# DMSMDS.net
KiCad netlist of a schematic drawn in EAGLE
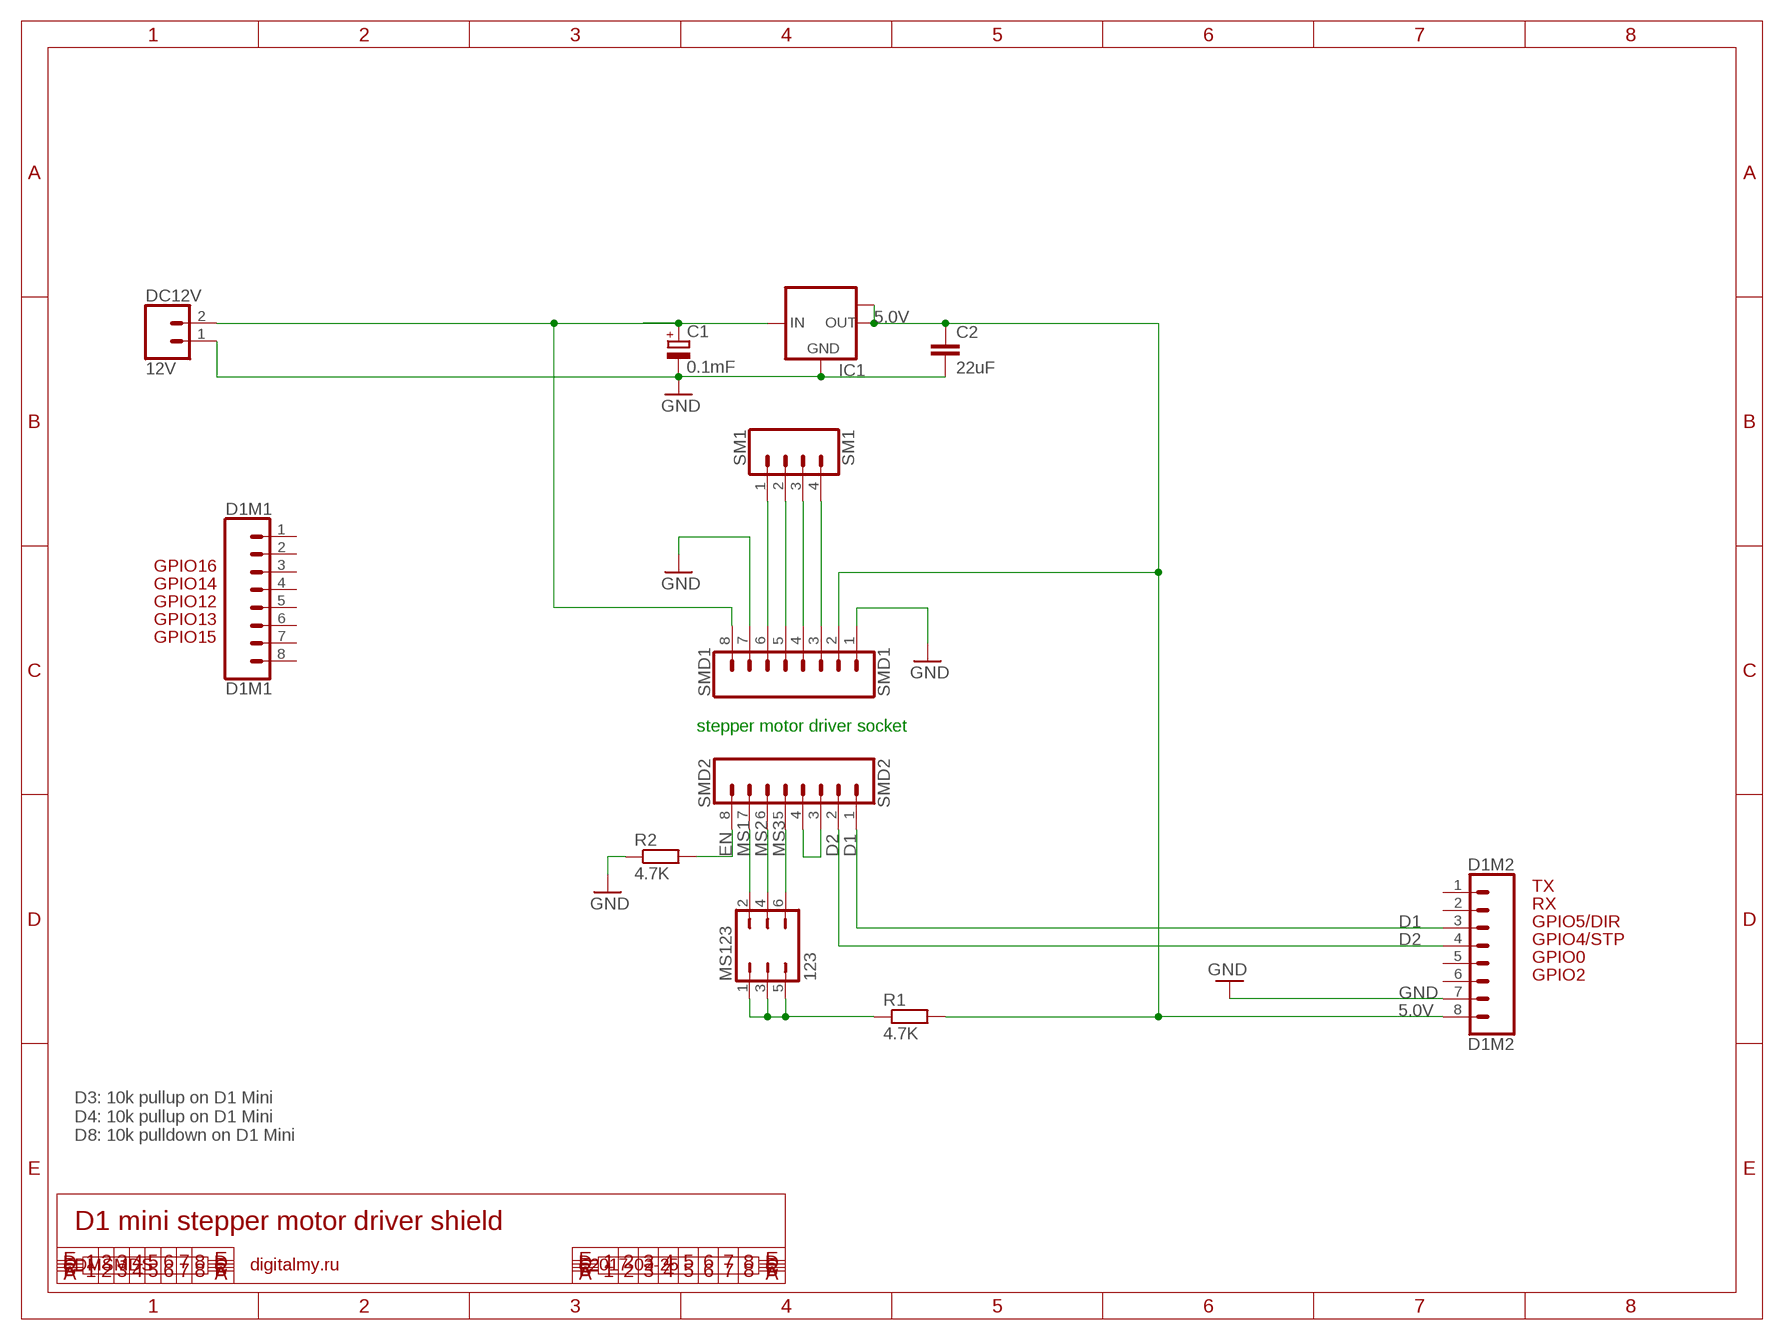
[diagram p0: schematic, sheet 1]

(export (version "E")
  (design (tool "Eeschema 10.0.6"))
  (components
    (comp (ref "C1")
      (value "0.1mF")
      (footprint "eagle-import:E5-8,5")
      (libsource (lib "eagle-import") (part "CPOL-EUE5-8.5"))
    )
    (comp (ref "C2")
      (value "22uF")
      (footprint "eagle-import:C1206")
      (libsource (lib "eagle-import") (part "C-EUC1206"))
    )
    (comp (ref "D1M1")
      (value "D1M1")
      (footprint "eagle-import:1X08")
      (libsource (lib "eagle-import") (part "CONN_08{dblquote}"))
    )
    (comp (ref "D1M2")
      (value "D1M2")
      (footprint "eagle-import:1X08")
      (libsource (lib "eagle-import") (part "CONN_08{dblquote}"))
    )
    (comp (ref "DC12V")
      (value "12V")
      (footprint "eagle-import:1X02")
      (libsource (lib "eagle-import") (part "CONN_02"))
    )
    (comp (ref "IC1")
      (value "LM1117MPX-5.0")
      (footprint "eagle-import:SOT223")
      (libsource (lib "eagle-import") (part "LM1117MPX-5.0"))
    )
    (comp (ref "MS123")
      (value "123")
      (footprint "eagle-import:JP3Q")
      (libsource (lib "eagle-import") (part "JP3Q"))
    )
    (comp (ref "R1")
      (value "4.7K")
      (footprint "eagle-import:R0402")
      (libsource (lib "eagle-import") (part "R-EU_R0402"))
    )
    (comp (ref "R2")
      (value "4.7K")
      (footprint "eagle-import:R0402")
      (libsource (lib "eagle-import") (part "R-EU_R0402"))
    )
    (comp (ref "SM1")
      (value "SM1")
      (footprint "eagle-import:1X04")
      (libsource (lib "eagle-import") (part "CONN_04"))
    )
    (comp (ref "SMD1")
      (value "SMD1")
      (footprint "eagle-import:1X08_NO_SILK")
      (libsource (lib "eagle-import") (part "CONN_08NO_SILK_FEMALE_PTH"))
    )
    (comp (ref "SMD2")
      (value "SMD2")
      (footprint "eagle-import:1X08_NO_SILK")
      (libsource (lib "eagle-import") (part "CONN_08NO_SILK_FEMALE_PTH"))
    )
  )
  (nets
    (net (code "1") (name "/5.0V") (class "Default")
      (node (ref "C2") (pin "1") (pinfunction "1_1") (pintype "passive"))
      (node (ref "D1M2") (pin "8") (pinfunction "8_8") (pintype "passive"))
      (node (ref "IC1") (pin "2") (pinfunction "OUT_2") (pintype "passive"))
      (node (ref "IC1") (pin "TAB") (pinfunction "OUT1_TAB") (pintype "passive"))
      (node (ref "R1") (pin "2") (pinfunction "2_2") (pintype "passive"))
      (node (ref "SMD1") (pin "2") (pinfunction "2_2") (pintype "passive"))
    )
    (net (code "2") (name "/D1") (class "Default")
      (node (ref "D1M2") (pin "3") (pinfunction "3_3") (pintype "passive"))
      (node (ref "SMD2") (pin "1") (pinfunction "1_1") (pintype "passive"))
    )
    (net (code "3") (name "/D2") (class "Default")
      (node (ref "D1M2") (pin "4") (pinfunction "4_4") (pintype "passive"))
      (node (ref "SMD2") (pin "2") (pinfunction "2_2") (pintype "passive"))
    )
    (net (code "4") (name "/EN") (class "Default")
      (node (ref "R2") (pin "2") (pinfunction "2_2") (pintype "passive"))
      (node (ref "SMD2") (pin "8") (pinfunction "8_8") (pintype "passive"))
    )
    (net (code "5") (name "/MS1") (class "Default")
      (node (ref "MS123") (pin "2") (pinfunction "2_2") (pintype "passive"))
      (node (ref "SMD2") (pin "7") (pinfunction "7_7") (pintype "passive"))
    )
    (net (code "6") (name "/MS2") (class "Default")
      (node (ref "MS123") (pin "4") (pinfunction "4_4") (pintype "passive"))
      (node (ref "SMD2") (pin "6") (pinfunction "6_6") (pintype "passive"))
    )
    (net (code "7") (name "/MS3") (class "Default")
      (node (ref "MS123") (pin "6") (pinfunction "6_6") (pintype "passive"))
      (node (ref "SMD2") (pin "5") (pinfunction "5_5") (pintype "passive"))
    )
    (net (code "8") (name "GND") (class "Default")
      (node (ref "C1") (pin "-") (pinfunction "-_-") (pintype "passive"))
      (node (ref "C2") (pin "2") (pinfunction "2_2") (pintype "passive"))
      (node (ref "D1M2") (pin "7") (pinfunction "7_7") (pintype "passive"))
      (node (ref "DC12V") (pin "1") (pinfunction "1_1") (pintype "passive"))
      (node (ref "IC1") (pin "1") (pinfunction "GND_1") (pintype "input"))
      (node (ref "R2") (pin "1") (pinfunction "1_1") (pintype "passive"))
      (node (ref "SMD1") (pin "1") (pinfunction "1_1") (pintype "passive"))
      (node (ref "SMD1") (pin "7") (pinfunction "7_7") (pintype "passive"))
    )
    (net (code "9") (name "Net-(IC1-IN)") (class "Default")
      (node (ref "C1") (pin "+") (pinfunction "+_+") (pintype "passive"))
      (node (ref "DC12V") (pin "2") (pinfunction "2_2") (pintype "passive"))
      (node (ref "IC1") (pin "3") (pinfunction "IN_3") (pintype "input"))
      (node (ref "SMD1") (pin "8") (pinfunction "8_8") (pintype "passive"))
    )
    (net (code "10") (name "Net-(MS123-Pad1)") (class "Default")
      (node (ref "MS123") (pin "1") (pinfunction "1_1") (pintype "passive"))
      (node (ref "MS123") (pin "3") (pinfunction "3_3") (pintype "passive"))
      (node (ref "MS123") (pin "5") (pinfunction "5_5") (pintype "passive"))
      (node (ref "R1") (pin "1") (pinfunction "1_1") (pintype "passive"))
    )
    (net (code "11") (name "Net-(SM1-Pad1)") (class "Default")
      (node (ref "SM1") (pin "1") (pinfunction "1_1") (pintype "passive"))
      (node (ref "SMD1") (pin "6") (pinfunction "6_6") (pintype "passive"))
    )
    (net (code "12") (name "Net-(SM1-Pad2)") (class "Default")
      (node (ref "SM1") (pin "2") (pinfunction "2_2") (pintype "passive"))
      (node (ref "SMD1") (pin "5") (pinfunction "5_5") (pintype "passive"))
    )
    (net (code "13") (name "Net-(SM1-Pad3)") (class "Default")
      (node (ref "SM1") (pin "3") (pinfunction "3_3") (pintype "passive"))
      (node (ref "SMD1") (pin "4") (pinfunction "4_4") (pintype "passive"))
    )
    (net (code "14") (name "Net-(SM1-Pad4)") (class "Default")
      (node (ref "SM1") (pin "4") (pinfunction "4_4") (pintype "passive"))
      (node (ref "SMD1") (pin "3") (pinfunction "3_3") (pintype "passive"))
    )
    (net (code "15") (name "Net-(SMD2-Pad3)") (class "Default")
      (node (ref "SMD2") (pin "3") (pinfunction "3_3") (pintype "passive"))
      (node (ref "SMD2") (pin "4") (pinfunction "4_4") (pintype "passive"))
    )
    (net (code "16") (name "unconnected-(D1M1-Pad1)") (class "Default")
      (node (ref "D1M1") (pin "1") (pinfunction "1_1") (pintype "passive"))
    )
    (net (code "17") (name "unconnected-(D1M1-Pad2)") (class "Default")
      (node (ref "D1M1") (pin "2") (pinfunction "2_2") (pintype "passive"))
    )
    (net (code "18") (name "unconnected-(D1M1-Pad3)") (class "Default")
      (node (ref "D1M1") (pin "3") (pinfunction "3_3") (pintype "passive"))
    )
    (net (code "19") (name "unconnected-(D1M1-Pad4)") (class "Default")
      (node (ref "D1M1") (pin "4") (pinfunction "4_4") (pintype "passive"))
    )
    (net (code "20") (name "unconnected-(D1M1-Pad5)") (class "Default")
      (node (ref "D1M1") (pin "5") (pinfunction "5_5") (pintype "passive"))
    )
    (net (code "21") (name "unconnected-(D1M1-Pad6)") (class "Default")
      (node (ref "D1M1") (pin "6") (pinfunction "6_6") (pintype "passive"))
    )
    (net (code "22") (name "unconnected-(D1M1-Pad7)") (class "Default")
      (node (ref "D1M1") (pin "7") (pinfunction "7_7") (pintype "passive"))
    )
    (net (code "23") (name "unconnected-(D1M1-Pad8)") (class "Default")
      (node (ref "D1M1") (pin "8") (pinfunction "8_8") (pintype "passive"))
    )
    (net (code "24") (name "unconnected-(D1M2-Pad1)") (class "Default")
      (node (ref "D1M2") (pin "1") (pinfunction "1_1") (pintype "passive"))
    )
    (net (code "25") (name "unconnected-(D1M2-Pad2)") (class "Default")
      (node (ref "D1M2") (pin "2") (pinfunction "2_2") (pintype "passive"))
    )
    (net (code "26") (name "unconnected-(D1M2-Pad5)") (class "Default")
      (node (ref "D1M2") (pin "5") (pinfunction "5_5") (pintype "passive"))
    )
    (net (code "27") (name "unconnected-(D1M2-Pad6)") (class "Default")
      (node (ref "D1M2") (pin "6") (pinfunction "6_6") (pintype "passive"))
    )
  )
)
